# MegaShieldTrio.net
KiCad netlist of a schematic drawn in EAGLE
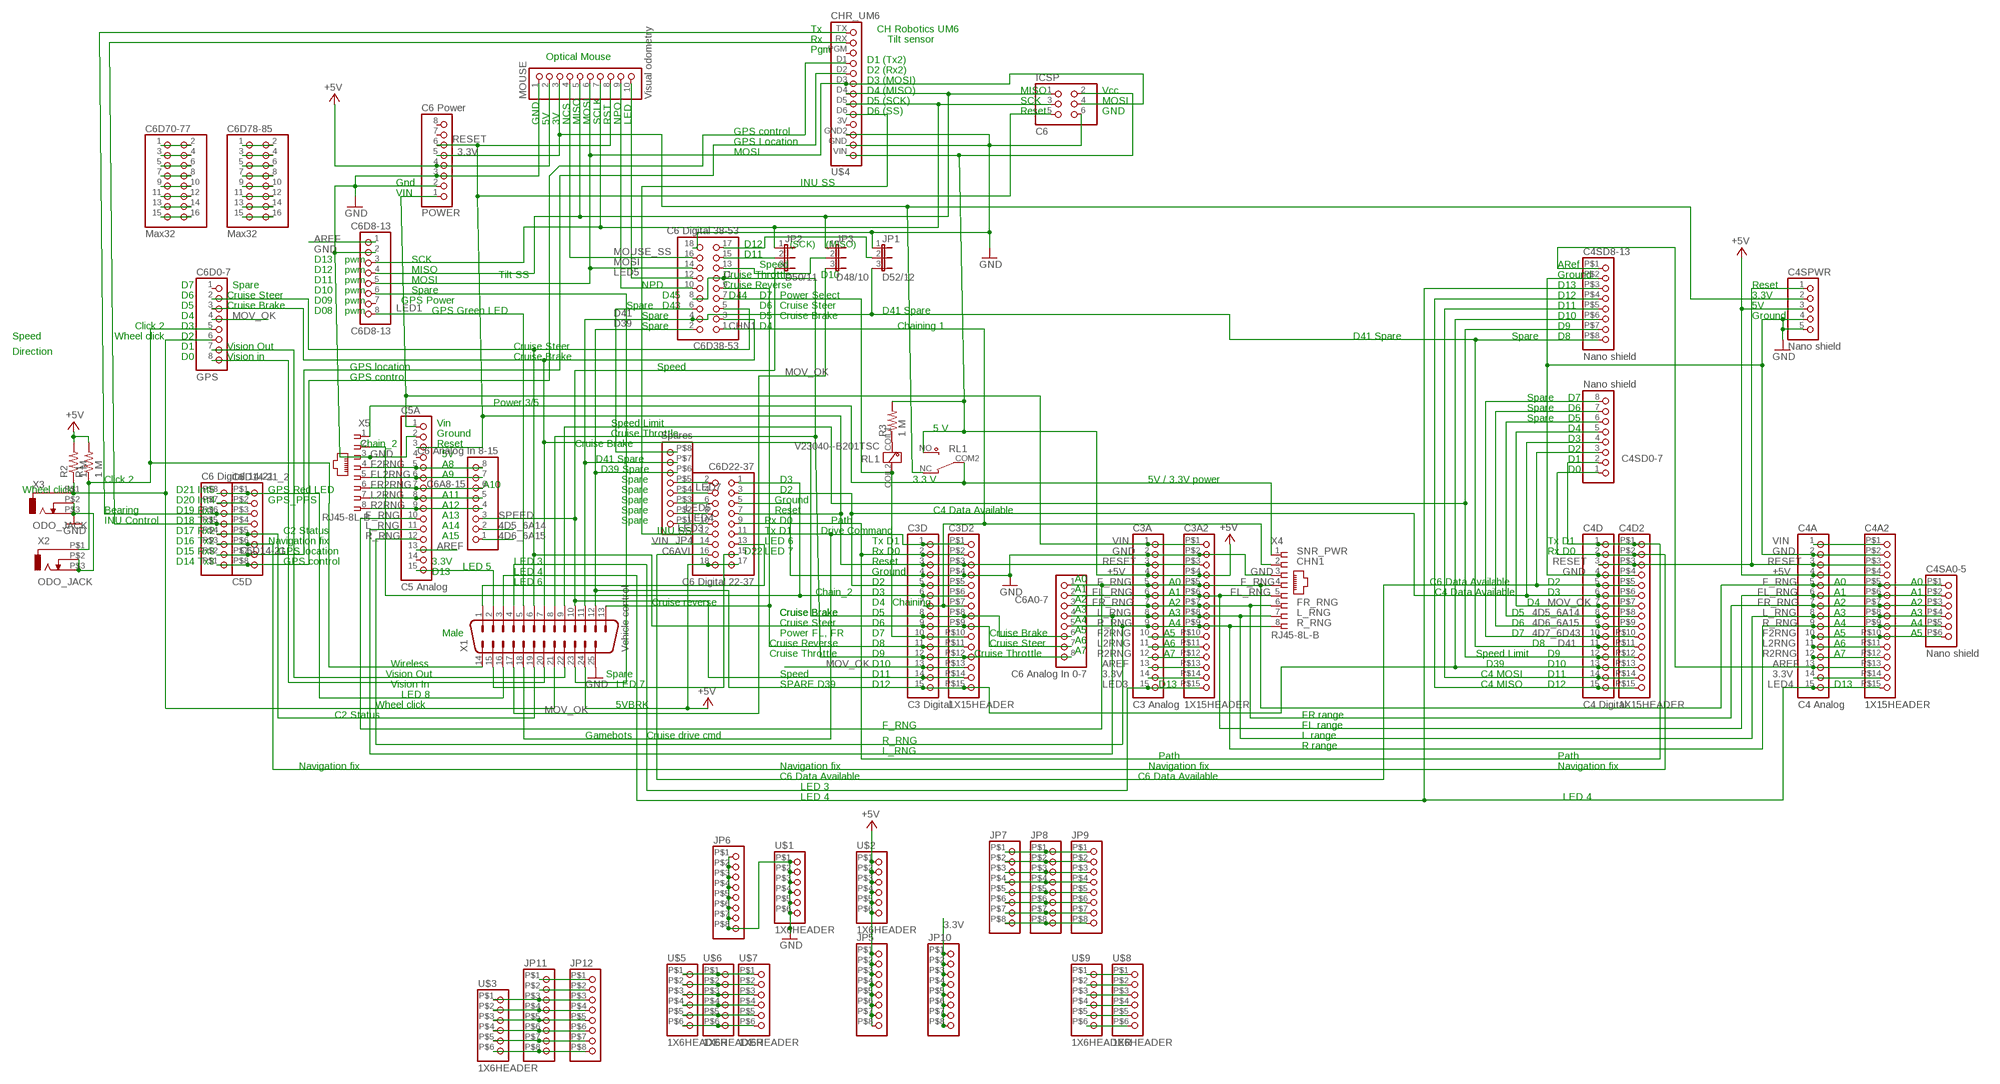
[diagram p0: schematic, sheet 1]

(export (version "E")
  (design (tool "Eeschema 10.0.6"))
  (components
    (comp (ref "C3A")
      (value "C3 Analog")
      (footprint "eagle-import:1X15")
      (libsource (lib "eagle-import") (part "PINHD-1X15"))
    )
    (comp (ref "C3A2")
      (value "1X15HEADER")
      (footprint "eagle-import:1X15HEADER")
      (libsource (lib "eagle-import") (part "1X15HEADER"))
    )
    (comp (ref "C3D")
      (value "C3 Digital")
      (footprint "eagle-import:1X15")
      (libsource (lib "eagle-import") (part "PINHD-1X15"))
    )
    (comp (ref "C3D2")
      (value "1X15HEADER")
      (footprint "eagle-import:1X15HEADER")
      (libsource (lib "eagle-import") (part "1X15HEADER"))
    )
    (comp (ref "C4A")
      (value "C4 Analog")
      (footprint "eagle-import:1X15")
      (libsource (lib "eagle-import") (part "PINHD-1X15"))
    )
    (comp (ref "C4A2")
      (value "1X15HEADER")
      (footprint "eagle-import:1X15HEADER")
      (libsource (lib "eagle-import") (part "1X15HEADER"))
    )
    (comp (ref "C4D")
      (value "C4 Digital")
      (footprint "eagle-import:1X15")
      (libsource (lib "eagle-import") (part "PINHD-1X15"))
    )
    (comp (ref "C4D2")
      (value "1X15HEADER")
      (footprint "eagle-import:1X15HEADER")
      (libsource (lib "eagle-import") (part "1X15HEADER"))
    )
    (comp (ref "C4SA0-5")
      (value "Nano shield")
      (footprint "eagle-import:1X6HEADER")
      (libsource (lib "eagle-import") (part "1X6HEADER"))
    )
    (comp (ref "C4SD0-7")
      (value "Nano shield")
      (footprint "eagle-import:1X08")
      (libsource (lib "eagle-import") (part "pinhead_PINHD-1X8"))
    )
    (comp (ref "C4SD8-13")
      (value "Nano shield")
      (footprint "eagle-import:1X8HEADER")
      (libsource (lib "eagle-import") (part "PINHD-1X8SMALL8"))
    )
    (comp (ref "C4SPWR")
      (value "Nano shield")
      (footprint "eagle-import:1X05")
      (libsource (lib "eagle-import") (part "PINHD-1X5"))
    )
    (comp (ref "C5A")
      (value "C5 Analog")
      (footprint "eagle-import:1X15")
      (libsource (lib "eagle-import") (part "PINHD-1X15"))
    )
    (comp (ref "C6A0-7")
      (value "C6 Analog In 0-7")
      (footprint "eagle-import:1X08")
      (libsource (lib "eagle-import") (part "pinhead_PINHD-1X8"))
    )
    (comp (ref "C6A8-15")
      (value "C6 Analog In 8-15")
      (footprint "eagle-import:1X08")
      (libsource (lib "eagle-import") (part "pinhead_PINHD-1X8"))
    )
    (comp (ref "C6D0-7")
      (value "GPS")
      (footprint "eagle-import:1X08")
      (libsource (lib "eagle-import") (part "pinhead_PINHD-1X8"))
    )
    (comp (ref "C6D8-13")
      (value "C6D8-13")
      (footprint "eagle-import:1X08")
      (libsource (lib "eagle-import") (part "pinhead_PINHD-1X8"))
    )
    (comp (ref "C6D14-21")
      (value "C6 Digital 14-21")
      (footprint "eagle-import:1X8HEADER")
      (libsource (lib "eagle-import") (part "PINHD-1X8SMALL8"))
    )
    (comp (ref "C6D14-21_2")
      (value "C5D")
      (footprint "eagle-import:1X8HEADER")
      (libsource (lib "eagle-import") (part "PINHD-1X8SMALL8"))
    )
    (comp (ref "C6D22-37")
      (value "C6 Digital 22-37")
      (footprint "eagle-import:2X09")
      (libsource (lib "eagle-import") (part "PINHD-2X9"))
    )
    (comp (ref "C6D38-53")
      (value "C6 Digital 38-53")
      (footprint "eagle-import:2X09")
      (libsource (lib "eagle-import") (part "PINHD-2X9"))
    )
    (comp (ref "C6D70-77")
      (value "Max32")
      (footprint "eagle-import:2X08")
      (libsource (lib "eagle-import") (part "PINHD-2X8"))
    )
    (comp (ref "C6D78-85")
      (value "Max32")
      (footprint "eagle-import:2X08")
      (libsource (lib "eagle-import") (part "PINHD-2X8"))
    )
    (comp (ref "ICSP")
      (value "C6")
      (footprint "eagle-import:2X03")
      (libsource (lib "eagle-import") (part "PINHD-2X3"))
    )
    (comp (ref "JP1")
      (value "D52/12")
      (footprint "eagle-import:JP2")
      (libsource (lib "eagle-import") (part "JP2E"))
    )
    (comp (ref "JP2")
      (value "D50/11")
      (footprint "eagle-import:JP2")
      (libsource (lib "eagle-import") (part "JP2E"))
    )
    (comp (ref "JP3")
      (value "D48/10")
      (footprint "eagle-import:JP2")
      (libsource (lib "eagle-import") (part "JP2E"))
    )
    (comp (ref "JP4")
      (value "Spares")
      (footprint "eagle-import:1X8HEADER")
      (libsource (lib "eagle-import") (part "PINHD-1X8SMALL8"))
    )
    (comp (ref "JP5")
      (value "PINHD-1X8SMALL8")
      (footprint "eagle-import:1X8HEADER")
      (libsource (lib "eagle-import") (part "PINHD-1X8SMALL8"))
    )
    (comp (ref "JP6")
      (value "PINHD-1X8SMALL8")
      (footprint "eagle-import:1X8HEADER")
      (libsource (lib "eagle-import") (part "PINHD-1X8SMALL8"))
    )
    (comp (ref "JP7")
      (value "PINHD-1X8SMALL8")
      (footprint "eagle-import:1X8HEADER")
      (libsource (lib "eagle-import") (part "PINHD-1X8SMALL8"))
    )
    (comp (ref "JP8")
      (value "PINHD-1X8SMALL8")
      (footprint "eagle-import:1X8HEADER")
      (libsource (lib "eagle-import") (part "PINHD-1X8SMALL8"))
    )
    (comp (ref "JP9")
      (value "PINHD-1X8SMALL8")
      (footprint "eagle-import:1X8HEADER")
      (libsource (lib "eagle-import") (part "PINHD-1X8SMALL8"))
    )
    (comp (ref "JP10")
      (value "PINHD-1X8SMALL8")
      (footprint "eagle-import:1X8HEADER")
      (libsource (lib "eagle-import") (part "PINHD-1X8SMALL8"))
    )
    (comp (ref "JP11")
      (value "PINHD-1X8SMALL8")
      (footprint "eagle-import:1X8HEADER")
      (libsource (lib "eagle-import") (part "PINHD-1X8SMALL8"))
    )
    (comp (ref "JP12")
      (value "PINHD-1X8SMALL8")
      (footprint "eagle-import:1X8HEADER")
      (libsource (lib "eagle-import") (part "PINHD-1X8SMALL8"))
    )
    (comp (ref "MOUSE")
      (value "Visual odometry")
      (footprint "eagle-import:1X10")
      (libsource (lib "eagle-import") (part "PINHD-1X10"))
    )
    (comp (ref "POWER")
      (value "C6 Power")
      (footprint "eagle-import:1X08")
      (libsource (lib "eagle-import") (part "pinhead_PINHD-1X8"))
    )
    (comp (ref "R1")
      (value "1 M")
      (footprint "eagle-import:0207_10")
      (libsource (lib "eagle-import") (part "R-US_0207/10"))
    )
    (comp (ref "R2")
      (value "1 M")
      (footprint "eagle-import:0207_10")
      (libsource (lib "eagle-import") (part "R-US_0207/10"))
    )
    (comp (ref "R3")
      (value "1 M")
      (footprint "eagle-import:0207_10")
      (libsource (lib "eagle-import") (part "R-US_0207/10"))
    )
    (comp (ref "RL1")
      (value "V23040--B201TSC")
      (footprint "eagle-import:TSC-112L3H")
      (libsource (lib "eagle-import") (part "V23040--B201TSC"))
    )
    (comp (ref "U$1")
      (value "1X6HEADER")
      (footprint "eagle-import:1X6HEADER")
      (libsource (lib "eagle-import") (part "1X6HEADER"))
    )
    (comp (ref "U$2")
      (value "1X6HEADER")
      (footprint "eagle-import:1X6HEADER")
      (libsource (lib "eagle-import") (part "1X6HEADER"))
    )
    (comp (ref "U$3")
      (value "1X6HEADER")
      (footprint "eagle-import:1X6HEADER")
      (libsource (lib "eagle-import") (part "1X6HEADER"))
    )
    (comp (ref "U$4")
      (value "CHR_UM6")
      (footprint "eagle-import:CHR_UM6")
      (libsource (lib "eagle-import") (part "CHR_UM6"))
    )
    (comp (ref "U$5")
      (value "1X6HEADER")
      (footprint "eagle-import:1X6HEADER")
      (libsource (lib "eagle-import") (part "1X6HEADER"))
    )
    (comp (ref "U$6")
      (value "1X6HEADER")
      (footprint "eagle-import:1X6HEADER")
      (libsource (lib "eagle-import") (part "1X6HEADER"))
    )
    (comp (ref "U$7")
      (value "1X6HEADER")
      (footprint "eagle-import:1X6HEADER")
      (libsource (lib "eagle-import") (part "1X6HEADER"))
    )
    (comp (ref "U$8")
      (value "1X6HEADER")
      (footprint "eagle-import:1X6HEADER")
      (libsource (lib "eagle-import") (part "1X6HEADER"))
    )
    (comp (ref "U$9")
      (value "1X6HEADER")
      (footprint "eagle-import:1X6HEADER")
      (libsource (lib "eagle-import") (part "1X6HEADER"))
    )
    (comp (ref "X1")
      (value "Vehicle control")
      (footprint "eagle-import:M25H")
      (libsource (lib "eagle-import") (part "M25H"))
    )
    (comp (ref "X2")
      (value "ODO_JACK")
      (footprint "eagle-import:ODO_JACK")
      (libsource (lib "eagle-import") (part "ODO_JACK"))
    )
    (comp (ref "X3")
      (value "ODO_JACK")
      (footprint "eagle-import:ODO_JACK")
      (libsource (lib "eagle-import") (part "ODO_JACK"))
    )
    (comp (ref "X4")
      (value "RJ45-8L-B")
      (footprint "eagle-import:RJ45-NO-SHIELD")
      (fields (field (name "MF") "TYCO ELECTRONICS"))
      (libsource (lib "eagle-import") (part "RJ45-8L-B"))
    )
    (comp (ref "X5")
      (value "RJ45-8L-B")
      (footprint "eagle-import:RJ45-NO-SHIELD")
      (fields (field (name "MF") "TYCO ELECTRONICS"))
      (libsource (lib "eagle-import") (part "RJ45-8L-B"))
    )
  )
  (nets
    (net (code "1") (name "+5V") (class "Default")
      (node (ref "C3A") (pin "4") (pinfunction "4_4") (pintype "passive"))
      (node (ref "C3A2") (pin "P$4") (pinfunction "4_P$4") (pintype "passive"))
      (node (ref "C4A") (pin "4") (pinfunction "4_4") (pintype "passive"))
      (node (ref "C4A2") (pin "P$4") (pinfunction "4_P$4") (pintype "passive"))
      (node (ref "C4SPWR") (pin "3") (pinfunction "3_3") (pintype "passive"))
      (node (ref "C6D22-37") (pin "17") (pinfunction "17_17") (pintype "passive"))
      (node (ref "C6D22-37") (pin "18") (pinfunction "18_18") (pintype "passive"))
      (node (ref "ICSP") (pin "2") (pinfunction "2_2") (pintype "passive"))
      (node (ref "JP5") (pin "P$1") (pinfunction "1_P$1") (pintype "passive"))
      (node (ref "JP5") (pin "P$2") (pinfunction "2_P$2") (pintype "passive"))
      (node (ref "JP5") (pin "P$3") (pinfunction "3_P$3") (pintype "passive"))
      (node (ref "JP5") (pin "P$4") (pinfunction "4_P$4") (pintype "passive"))
      (node (ref "JP5") (pin "P$5") (pinfunction "5_P$5") (pintype "passive"))
      (node (ref "JP5") (pin "P$6") (pinfunction "6_P$6") (pintype "passive"))
      (node (ref "JP5") (pin "P$7") (pinfunction "7_P$7") (pintype "passive"))
      (node (ref "JP5") (pin "P$8") (pinfunction "8_P$8") (pintype "passive"))
      (node (ref "MOUSE") (pin "2") (pinfunction "2_2") (pintype "passive"))
      (node (ref "POWER") (pin "4") (pinfunction "4_4") (pintype "passive"))
      (node (ref "R1") (pin "2") (pinfunction "2_2") (pintype "passive"))
      (node (ref "R2") (pin "2") (pinfunction "2_2") (pintype "passive"))
      (node (ref "R3") (pin "2") (pinfunction "2_2") (pintype "passive"))
      (node (ref "RL1") (pin "NO") (pinfunction "6_NO") (pintype "passive"))
      (node (ref "U$2") (pin "P$1") (pinfunction "1_P$1") (pintype "passive"))
      (node (ref "U$2") (pin "P$2") (pinfunction "2_P$2") (pintype "passive"))
      (node (ref "U$2") (pin "P$3") (pinfunction "3_P$3") (pintype "passive"))
      (node (ref "U$2") (pin "P$4") (pinfunction "4_P$4") (pintype "passive"))
      (node (ref "U$2") (pin "P$5") (pinfunction "5_P$5") (pintype "passive"))
      (node (ref "U$2") (pin "P$6") (pinfunction "6_P$6") (pintype "passive"))
      (node (ref "U$4") (pin "VIN") (pinfunction "1_VIN") (pintype "passive"))
      (node (ref "X1") (pin "24") (pinfunction "24_24") (pintype "passive"))
    )
    (net (code "2") (name "/3.3V") (class "Default")
      (node (ref "C3A") (pin "14") (pinfunction "14_14") (pintype "passive"))
      (node (ref "C3A2") (pin "P$14") (pinfunction "14_P$14") (pintype "passive"))
      (node (ref "C4A") (pin "14") (pinfunction "14_14") (pintype "passive"))
      (node (ref "C4A2") (pin "P$14") (pinfunction "14_P$14") (pintype "passive"))
      (node (ref "C4SPWR") (pin "2") (pinfunction "2_2") (pintype "passive"))
      (node (ref "JP10") (pin "P$1") (pinfunction "1_P$1") (pintype "passive"))
      (node (ref "JP10") (pin "P$2") (pinfunction "2_P$2") (pintype "passive"))
      (node (ref "JP10") (pin "P$3") (pinfunction "3_P$3") (pintype "passive"))
      (node (ref "JP10") (pin "P$4") (pinfunction "4_P$4") (pintype "passive"))
      (node (ref "JP10") (pin "P$5") (pinfunction "5_P$5") (pintype "passive"))
      (node (ref "JP10") (pin "P$6") (pinfunction "6_P$6") (pintype "passive"))
      (node (ref "JP10") (pin "P$7") (pinfunction "7_P$7") (pintype "passive"))
      (node (ref "JP10") (pin "P$8") (pinfunction "8_P$8") (pintype "passive"))
      (node (ref "MOUSE") (pin "3") (pinfunction "3_3") (pintype "passive"))
      (node (ref "POWER") (pin "5") (pinfunction "5_5") (pintype "passive"))
      (node (ref "RL1") (pin "NC") (pinfunction "4_NC") (pintype "passive"))
    )
    (net (code "3") (name "/4D5_6A14") (class "Default")
      (node (ref "C4D") (pin "8") (pinfunction "8_8") (pintype "passive"))
      (node (ref "C4D2") (pin "P$8") (pinfunction "8_P$8") (pintype "passive"))
      (node (ref "C4SD0-7") (pin "6") (pinfunction "6_6") (pintype "passive"))
      (node (ref "C6A8-15") (pin "2") (pinfunction "2_2") (pintype "passive"))
    )
    (net (code "4") (name "/4D6_6A15") (class "Default")
      (node (ref "C4D") (pin "9") (pinfunction "9_9") (pintype "passive"))
      (node (ref "C4D2") (pin "P$9") (pinfunction "9_P$9") (pintype "passive"))
      (node (ref "C4SD0-7") (pin "7") (pinfunction "7_7") (pintype "passive"))
      (node (ref "C6A8-15") (pin "1") (pinfunction "1_1") (pintype "passive"))
    )
    (net (code "5") (name "/4D7_6D43") (class "Default")
      (node (ref "C4D") (pin "10") (pinfunction "10_10") (pintype "passive"))
      (node (ref "C4D2") (pin "P$10") (pinfunction "10_P$10") (pintype "passive"))
      (node (ref "C4SD0-7") (pin "8") (pinfunction "8_8") (pintype "passive"))
    )
    (net (code "6") (name "/AREF") (class "Default")
      (node (ref "C3A") (pin "13") (pinfunction "13_13") (pintype "passive"))
      (node (ref "C3A2") (pin "P$13") (pinfunction "13_P$13") (pintype "passive"))
      (node (ref "C4A") (pin "13") (pinfunction "13_13") (pintype "passive"))
      (node (ref "C4A2") (pin "P$13") (pinfunction "13_P$13") (pintype "passive"))
      (node (ref "C4SD8-13") (pin "P$1") (pinfunction "1_P$1") (pintype "passive"))
      (node (ref "C5A") (pin "13") (pinfunction "13_13") (pintype "passive"))
      (node (ref "C6D8-13") (pin "1") (pinfunction "1_1") (pintype "passive"))
    )
    (net (code "7") (name "/C6AVL") (class "Default")
      (node (ref "C4D") (pin "5") (pinfunction "5_5") (pintype "passive"))
      (node (ref "C4D2") (pin "P$5") (pinfunction "5_P$5") (pintype "passive"))
      (node (ref "C4SD0-7") (pin "3") (pinfunction "3_3") (pintype "passive"))
      (node (ref "C6D22-37") (pin "16") (pinfunction "16_16") (pintype "passive"))
    )
    (net (code "8") (name "/CHN1") (class "Default")
      (node (ref "C3D") (pin "7") (pinfunction "7_7") (pintype "passive"))
      (node (ref "C3D2") (pin "P$7") (pinfunction "7_P$7") (pintype "passive"))
      (node (ref "C6D38-53") (pin "1") (pinfunction "1_1") (pintype "passive"))
      (node (ref "X4") (pin "2") (pinfunction "2_2") (pintype "passive"))
    )
    (net (code "9") (name "/D39") (class "Default")
      (node (ref "C3D") (pin "15") (pinfunction "15_15") (pintype "passive"))
      (node (ref "C3D2") (pin "P$15") (pinfunction "15_P$15") (pintype "passive"))
      (node (ref "C4D") (pin "13") (pinfunction "13_13") (pintype "passive"))
      (node (ref "C4D2") (pin "P$13") (pinfunction "13_P$13") (pintype "passive"))
      (node (ref "C4SD8-13") (pin "P$6") (pinfunction "6_P$6") (pintype "passive"))
      (node (ref "C6D38-53") (pin "2") (pinfunction "2_2") (pintype "passive"))
      (node (ref "JP4") (pin "P$6") (pinfunction "6_P$6") (pintype "passive"))
      (node (ref "X1") (pin "12") (pinfunction "12_12") (pintype "passive"))
    )
    (net (code "10") (name "/D41") (class "Default")
      (node (ref "C4D") (pin "11") (pinfunction "11_11") (pintype "passive"))
      (node (ref "C4D2") (pin "P$11") (pinfunction "11_P$11") (pintype "passive"))
      (node (ref "C4SD8-13") (pin "P$8") (pinfunction "8_P$8") (pintype "passive"))
      (node (ref "C6D38-53") (pin "4") (pinfunction "4_4") (pintype "passive"))
      (node (ref "JP1") (pin "3") (pinfunction "3_3") (pintype "passive"))
      (node (ref "JP4") (pin "P$7") (pinfunction "7_P$7") (pintype "passive"))
      (node (ref "X1") (pin "11") (pinfunction "11_11") (pintype "passive"))
    )
    (net (code "11") (name "/F2RNG") (class "Default")
      (node (ref "C3A") (pin "10") (pinfunction "10_10") (pintype "passive"))
      (node (ref "C3A2") (pin "P$10") (pinfunction "10_P$10") (pintype "passive"))
      (node (ref "C4A") (pin "10") (pinfunction "10_10") (pintype "passive"))
      (node (ref "C4A2") (pin "P$10") (pinfunction "10_P$10") (pintype "passive"))
      (node (ref "C4SA0-5") (pin "P$6") (pinfunction "6_P$6") (pintype "passive"))
      (node (ref "C5A") (pin "5") (pinfunction "5_5") (pintype "passive"))
      (node (ref "C6A8-15") (pin "8") (pinfunction "8_8") (pintype "passive"))
      (node (ref "X5") (pin "4") (pinfunction "4_4") (pintype "passive"))
    )
    (net (code "12") (name "/FL2RNG") (class "Default")
      (node (ref "C5A") (pin "6") (pinfunction "6_6") (pintype "passive"))
      (node (ref "C6A8-15") (pin "7") (pinfunction "7_7") (pintype "passive"))
      (node (ref "X5") (pin "5") (pinfunction "5_5") (pintype "passive"))
    )
    (net (code "13") (name "/FL_RNG") (class "Default")
      (node (ref "C3A") (pin "6") (pinfunction "6_6") (pintype "passive"))
      (node (ref "C3A2") (pin "P$6") (pinfunction "6_P$6") (pintype "passive"))
      (node (ref "C4A") (pin "6") (pinfunction "6_6") (pintype "passive"))
      (node (ref "C4A2") (pin "P$6") (pinfunction "6_P$6") (pintype "passive"))
      (node (ref "C4SA0-5") (pin "P$2") (pinfunction "2_P$2") (pintype "passive"))
      (node (ref "C6A0-7") (pin "2") (pinfunction "2_2") (pintype "passive"))
      (node (ref "X4") (pin "5") (pinfunction "5_5") (pintype "passive"))
    )
    (net (code "14") (name "/FR2RNG") (class "Default")
      (node (ref "C5A") (pin "7") (pinfunction "7_7") (pintype "passive"))
      (node (ref "C6A8-15") (pin "6") (pinfunction "6_6") (pintype "passive"))
      (node (ref "X5") (pin "6") (pinfunction "6_6") (pintype "passive"))
    )
    (net (code "15") (name "/FR_RNG") (class "Default")
      (node (ref "C3A") (pin "7") (pinfunction "7_7") (pintype "passive"))
      (node (ref "C3A2") (pin "P$7") (pinfunction "7_P$7") (pintype "passive"))
      (node (ref "C4A") (pin "7") (pinfunction "7_7") (pintype "passive"))
      (node (ref "C4A2") (pin "P$7") (pinfunction "7_P$7") (pintype "passive"))
      (node (ref "C4SA0-5") (pin "P$3") (pinfunction "3_P$3") (pintype "passive"))
      (node (ref "C6A0-7") (pin "3") (pinfunction "3_3") (pintype "passive"))
      (node (ref "X4") (pin "6") (pinfunction "6_6") (pintype "passive"))
    )
    (net (code "16") (name "/F_RNG") (class "Default")
      (node (ref "C3A") (pin "5") (pinfunction "5_5") (pintype "passive"))
      (node (ref "C3A2") (pin "P$5") (pinfunction "5_P$5") (pintype "passive"))
      (node (ref "C4A") (pin "5") (pinfunction "5_5") (pintype "passive"))
      (node (ref "C4A2") (pin "P$5") (pinfunction "5_P$5") (pintype "passive"))
      (node (ref "C4SA0-5") (pin "P$1") (pinfunction "1_P$1") (pintype "passive"))
      (node (ref "C5A") (pin "10") (pinfunction "10_10") (pintype "passive"))
      (node (ref "C6A0-7") (pin "1") (pinfunction "1_1") (pintype "passive"))
      (node (ref "X4") (pin "4") (pinfunction "4_4") (pintype "passive"))
    )
    (net (code "17") (name "/L2RNG") (class "Default")
      (node (ref "C3A") (pin "11") (pinfunction "11_11") (pintype "passive"))
      (node (ref "C3A2") (pin "P$11") (pinfunction "11_P$11") (pintype "passive"))
      (node (ref "C4A") (pin "11") (pinfunction "11_11") (pintype "passive"))
      (node (ref "C4A2") (pin "P$11") (pinfunction "11_P$11") (pintype "passive"))
      (node (ref "C5A") (pin "8") (pinfunction "8_8") (pintype "passive"))
      (node (ref "C6A8-15") (pin "5") (pinfunction "5_5") (pintype "passive"))
      (node (ref "X5") (pin "7") (pinfunction "7_7") (pintype "passive"))
    )
    (net (code "18") (name "/LED1") (class "Default")
      (node (ref "C6D8-13") (pin "8") (pinfunction "8_8") (pintype "passive"))
      (node (ref "X1") (pin "5") (pinfunction "5_5") (pintype "passive"))
    )
    (net (code "19") (name "/LED3") (class "Default")
      (node (ref "C3A") (pin "15") (pinfunction "15_15") (pintype "passive"))
      (node (ref "C3A2") (pin "P$15") (pinfunction "15_P$15") (pintype "passive"))
      (node (ref "X1") (pin "4") (pinfunction "4_4") (pintype "passive"))
    )
    (net (code "20") (name "/LED4") (class "Default")
      (node (ref "C4A") (pin "15") (pinfunction "15_15") (pintype "passive"))
      (node (ref "C4A2") (pin "P$15") (pinfunction "15_P$15") (pintype "passive"))
      (node (ref "C4SD8-13") (pin "P$3") (pinfunction "3_P$3") (pintype "passive"))
      (node (ref "X1") (pin "3") (pinfunction "3_3") (pintype "passive"))
    )
    (net (code "21") (name "/LED5") (class "Default")
      (node (ref "C5A") (pin "15") (pinfunction "15_15") (pintype "passive"))
      (node (ref "C6D38-53") (pin "12") (pinfunction "12_12") (pintype "passive"))
      (node (ref "MOUSE") (pin "10") (pinfunction "10_10") (pintype "passive"))
      (node (ref "X1") (pin "2") (pinfunction "2_2") (pintype "passive"))
    )
    (net (code "22") (name "/LED7") (class "Default")
      (node (ref "C6D22-37") (pin "15") (pinfunction "15_15") (pintype "passive"))
      (node (ref "X1") (pin "15") (pinfunction "15_15") (pintype "passive"))
    )
    (net (code "23") (name "/L_RNG") (class "Default")
      (node (ref "C3A") (pin "8") (pinfunction "8_8") (pintype "passive"))
      (node (ref "C3A2") (pin "P$8") (pinfunction "8_P$8") (pintype "passive"))
      (node (ref "C4A") (pin "8") (pinfunction "8_8") (pintype "passive"))
      (node (ref "C4A2") (pin "P$8") (pinfunction "8_P$8") (pintype "passive"))
      (node (ref "C4SA0-5") (pin "P$4") (pinfunction "4_P$4") (pintype "passive"))
      (node (ref "C5A") (pin "11") (pinfunction "11_11") (pintype "passive"))
      (node (ref "C6A0-7") (pin "4") (pinfunction "4_4") (pintype "passive"))
      (node (ref "X4") (pin "7") (pinfunction "7_7") (pintype "passive"))
    )
    (net (code "24") (name "/MOSI") (class "Default")
      (node (ref "C6D38-53") (pin "14") (pinfunction "14_14") (pintype "passive"))
      (node (ref "C6D8-13") (pin "5") (pinfunction "5_5") (pintype "passive"))
      (node (ref "ICSP") (pin "4") (pinfunction "4_4") (pintype "passive"))
      (node (ref "MOUSE") (pin "6") (pinfunction "6_6") (pintype "passive"))
      (node (ref "U$4") (pin "D3") (pinfunction "8_D3") (pintype "passive"))
    )
    (net (code "25") (name "/MOUSE_SS") (class "Default")
      (node (ref "C6D38-53") (pin "16") (pinfunction "16_16") (pintype "passive"))
      (node (ref "MOUSE") (pin "4") (pinfunction "4_4") (pintype "passive"))
    )
    (net (code "26") (name "/MOV_OK") (class "Default")
      (node (ref "C3D") (pin "13") (pinfunction "13_13") (pintype "passive"))
      (node (ref "C3D2") (pin "P$13") (pinfunction "13_P$13") (pintype "passive"))
      (node (ref "C4D") (pin "7") (pinfunction "7_7") (pintype "passive"))
      (node (ref "C4D2") (pin "P$7") (pinfunction "7_P$7") (pintype "passive"))
      (node (ref "C4SD0-7") (pin "5") (pinfunction "5_5") (pintype "passive"))
      (node (ref "C6D0-7") (pin "4") (pinfunction "4_4") (pintype "passive"))
      (node (ref "JP3") (pin "3") (pinfunction "3_3") (pintype "passive"))
      (node (ref "X1") (pin "17") (pinfunction "17_17") (pintype "passive"))
    )
    (net (code "27") (name "/R2RNG") (class "Default")
      (node (ref "C3A") (pin "12") (pinfunction "12_12") (pintype "passive"))
      (node (ref "C3A2") (pin "P$12") (pinfunction "12_P$12") (pintype "passive"))
      (node (ref "C4A") (pin "12") (pinfunction "12_12") (pintype "passive"))
      (node (ref "C4A2") (pin "P$12") (pinfunction "12_P$12") (pintype "passive"))
      (node (ref "C5A") (pin "9") (pinfunction "9_9") (pintype "passive"))
      (node (ref "C6A8-15") (pin "4") (pinfunction "4_4") (pintype "passive"))
      (node (ref "X5") (pin "8") (pinfunction "8_8") (pintype "passive"))
    )
    (net (code "28") (name "/RESET") (class "Default")
      (node (ref "C3A") (pin "3") (pinfunction "3_3") (pintype "passive"))
      (node (ref "C3A2") (pin "P$3") (pinfunction "3_P$3") (pintype "passive"))
      (node (ref "C3D") (pin "3") (pinfunction "3_3") (pintype "passive"))
      (node (ref "C3D2") (pin "P$3") (pinfunction "3_P$3") (pintype "passive"))
      (node (ref "C4A") (pin "3") (pinfunction "3_3") (pintype "passive"))
      (node (ref "C4A2") (pin "P$3") (pinfunction "3_P$3") (pintype "passive"))
      (node (ref "C4D") (pin "3") (pinfunction "3_3") (pintype "passive"))
      (node (ref "C4D2") (pin "P$3") (pinfunction "3_P$3") (pintype "passive"))
      (node (ref "C4SPWR") (pin "1") (pinfunction "1_1") (pintype "passive"))
      (node (ref "C5A") (pin "3") (pinfunction "3_3") (pintype "passive"))
      (node (ref "C6D22-37") (pin "7") (pinfunction "7_7") (pintype "passive"))
      (node (ref "ICSP") (pin "5") (pinfunction "5_5") (pintype "passive"))
      (node (ref "MOUSE") (pin "8") (pinfunction "8_8") (pintype "passive"))
      (node (ref "POWER") (pin "6") (pinfunction "6_6") (pintype "passive"))
    )
    (net (code "29") (name "/R_RNG") (class "Default")
      (node (ref "C3A") (pin "9") (pinfunction "9_9") (pintype "passive"))
      (node (ref "C3A2") (pin "P$9") (pinfunction "9_P$9") (pintype "passive"))
      (node (ref "C4A") (pin "9") (pinfunction "9_9") (pintype "passive"))
      (node (ref "C4A2") (pin "P$9") (pinfunction "9_P$9") (pintype "passive"))
      (node (ref "C4SA0-5") (pin "P$5") (pinfunction "5_P$5") (pintype "passive"))
      (node (ref "C5A") (pin "12") (pinfunction "12_12") (pintype "passive"))
      (node (ref "C6A0-7") (pin "5") (pinfunction "5_5") (pintype "passive"))
      (node (ref "X4") (pin "8") (pinfunction "8_8") (pintype "passive"))
    )
    (net (code "30") (name "/SNR_PWR") (class "Default")
      (node (ref "RL1") (pin "COM2") (pinfunction "5_COM2") (pintype "passive"))
      (node (ref "X4") (pin "1") (pinfunction "1_1") (pintype "passive"))
      (node (ref "X5") (pin "1") (pinfunction "1_1") (pintype "passive"))
    )
    (net (code "31") (name "/SPEED") (class "Default")
      (node (ref "C3D") (pin "14") (pinfunction "14_14") (pintype "passive"))
      (node (ref "C3D2") (pin "P$14") (pinfunction "14_P$14") (pintype "passive"))
      (node (ref "C6A8-15") (pin "3") (pinfunction "3_3") (pintype "passive"))
      (node (ref "JP2") (pin "3") (pinfunction "3_3") (pintype "passive"))
      (node (ref "X1") (pin "10") (pinfunction "10_10") (pintype "passive"))
    )
    (net (code "32") (name "/VIN") (class "Default")
      (node (ref "C3A") (pin "1") (pinfunction "1_1") (pintype "passive"))
      (node (ref "C3A2") (pin "P$1") (pinfunction "1_P$1") (pintype "passive"))
      (node (ref "C4A") (pin "1") (pinfunction "1_1") (pintype "passive"))
      (node (ref "C4A2") (pin "P$1") (pinfunction "1_P$1") (pintype "passive"))
      (node (ref "C5A") (pin "1") (pinfunction "1_1") (pintype "passive"))
      (node (ref "C6D22-37") (pin "14") (pinfunction "14_14") (pintype "passive"))
      (node (ref "POWER") (pin "1") (pinfunction "1_1") (pintype "passive"))
    )
    (net (code "33") (name "GND") (class "Default")
      (node (ref "C3A") (pin "2") (pinfunction "2_2") (pintype "passive"))
      (node (ref "C3A2") (pin "P$2") (pinfunction "2_P$2") (pintype "passive"))
      (node (ref "C3D") (pin "4") (pinfunction "4_4") (pintype "passive"))
      (node (ref "C3D2") (pin "P$4") (pinfunction "4_P$4") (pintype "passive"))
      (node (ref "C4A") (pin "2") (pinfunction "2_2") (pintype "passive"))
      (node (ref "C4A2") (pin "P$2") (pinfunction "2_P$2") (pintype "passive"))
      (node (ref "C4D") (pin "4") (pinfunction "4_4") (pintype "passive"))
      (node (ref "C4D2") (pin "P$4") (pinfunction "4_P$4") (pintype "passive"))
      (node (ref "C4SD8-13") (pin "P$2") (pinfunction "2_P$2") (pintype "passive"))
      (node (ref "C4SPWR") (pin "4") (pinfunction "4_4") (pintype "passive"))
      (node (ref "C4SPWR") (pin "5") (pinfunction "5_5") (pintype "passive"))
      (node (ref "C5A") (pin "2") (pinfunction "2_2") (pintype "passive"))
      (node (ref "C6D22-37") (pin "5") (pinfunction "5_5") (pintype "passive"))
      (node (ref "C6D38-53") (pin "18") (pinfunction "18_18") (pintype "passive"))
      (node (ref "C6D8-13") (pin "2") (pinfunction "2_2") (pintype "passive"))
      (node (ref "ICSP") (pin "6") (pinfunction "6_6") (pintype "passive"))
      (node (ref "JP1") (pin "1") (pinfunction "1_1") (pintype "passive"))
      (node (ref "JP6") (pin "P$1") (pinfunction "1_P$1") (pintype "passive"))
      (node (ref "JP6") (pin "P$2") (pinfunction "2_P$2") (pintype "passive"))
      (node (ref "JP6") (pin "P$3") (pinfunction "3_P$3") (pintype "passive"))
      (node (ref "JP6") (pin "P$4") (pinfunction "4_P$4") (pintype "passive"))
      (node (ref "JP6") (pin "P$5") (pinfunction "5_P$5") (pintype "passive"))
      (node (ref "JP6") (pin "P$6") (pinfunction "6_P$6") (pintype "passive"))
      (node (ref "JP6") (pin "P$7") (pinfunction "7_P$7") (pintype "passive"))
      (node (ref "JP6") (pin "P$8") (pinfunction "8_P$8") (pintype "passive"))
      (node (ref "MOUSE") (pin "1") (pinfunction "1_1") (pintype "passive"))
      (node (ref "POWER") (pin "2") (pinfunction "2_2") (pintype "passive"))
      (node (ref "POWER") (pin "3") (pinfunction "3_3") (pintype "passive"))
      (node (ref "U$1") (pin "P$1") (pinfunction "1_P$1") (pintype "passive"))
      (node (ref "U$1") (pin "P$2") (pinfunction "2_P$2") (pintype "passive"))
      (node (ref "U$1") (pin "P$3") (pinfunction "3_P$3") (pintype "passive"))
      (node (ref "U$1") (pin "P$4") (pinfunction "4_P$4") (pintype "passive"))
      (node (ref "U$1") (pin "P$5") (pinfunction "5_P$5") (pintype "passive"))
      (node (ref "U$1") (pin "P$6") (pinfunction "6_P$6") (pintype "passive"))
      (node (ref "U$4") (pin "GND") (pinfunction "2_GND") (pintype "passive"))
      (node (ref "U$4") (pin "GND2") (pinfunction "3_GND2") (pintype "passive"))
      (node (ref "X1") (pin "25") (pinfunction "25_25") (pintype "passive"))
      (node (ref "X2") (pin "P$2") (pinfunction "2_P$2") (pintype "passive"))
      (node (ref "X2") (pin "P$3") (pinfunction "3_P$3") (pintype "passive"))
      (node (ref "X3") (pin "P$2") (pinfunction "2_P$2") (pintype "passive"))
      (node (ref "X3") (pin "P$3") (pinfunction "3_P$3") (pintype "passive"))
      (node (ref "X4") (pin "3") (pinfunction "3_3") (pintype "passive"))
      (node (ref "X5") (pin "3") (pinfunction "3_3") (pintype "passive"))
    )
    (net (code "34") (name "Net-(C3D2-1)") (class "Default")
      (node (ref "C3D") (pin "1") (pinfunction "1_1") (pintype "passive"))
      (node (ref "C3D2") (pin "P$1") (pinfunction "1_P$1") (pintype "passive"))
      (node (ref "C6D22-37") (pin "11") (pinfunction "11_11") (pintype "passive"))
      (node (ref "X1") (pin "18") (pinfunction "18_18") (pintype "passive"))
    )
    (net (code "35") (name "Net-(C3D2-2)") (class "Default")
      (node (ref "C3D") (pin "2") (pinfunction "2_2") (pintype "passive"))
      (node (ref "C3D2") (pin "P$2") (pinfunction "2_P$2") (pintype "passive"))
      (node (ref "C4D") (pin "1") (pinfunction "1_1") (pintype "passive"))
      (node (ref "C4D2") (pin "P$1") (pinfunction "1_P$1") (pintype "passive"))
      (node (ref "C4SD0-7") (pin "2") (pinfunction "2_2") (pintype "passive"))
      (node (ref "C6D22-37") (pin "9") (pinfunction "9_9") (pintype "passive"))
    )
    (net (code "36") (name "Net-(C3D2-5)") (class "Default")
      (node (ref "C3D") (pin "5") (pinfunction "5_5") (pintype "passive"))
      (node (ref "C3D2") (pin "P$5") (pinfunction "5_P$5") (pintype "passive"))
      (node (ref "C4D") (pin "6") (pinfunction "6_6") (pintype "passive"))
      (node (ref "C4D2") (pin "P$6") (pinfunction "6_P$6") (pintype "passive"))
      (node (ref "C4SD0-7") (pin "4") (pinfunction "4_4") (pintype "passive"))
      (node (ref "C6D22-37") (pin "3") (pinfunction "3_3") (pintype "passive"))
    )
    (net (code "37") (name "Net-(C3D2-6)") (class "Default")
      (node (ref "C3D") (pin "6") (pinfunction "6_6") (pintype "passive"))
      (node (ref "C3D2") (pin "P$6") (pinfunction "6_P$6") (pintype "passive"))
      (node (ref "C6D22-37") (pin "1") (pinfunction "1_1") (pintype "passive"))
      (node (ref "X5") (pin "2") (pinfunction "2_2") (pintype "passive"))
    )
    (net (code "38") (name "Net-(C3D2-8)") (class "Default")
      (node (ref "C3D") (pin "8") (pinfunction "8_8") (pintype "passive"))
      (node (ref "C3D2") (pin "P$8") (pinfunction "8_P$8") (pintype "passive"))
      (node (ref "C6A0-7") (pin "6") (pinfunction "6_6") (pintype "passive"))
      (node (ref "C6D0-7") (pin "3") (pinfunction "3_3") (pintype "passive"))
      (node (ref "C6D38-53") (pin "3") (pinfunction "3_3") (pintype "passive"))
      (node (ref "X1") (pin "7") (pinfunction "7_7") (pintype "passive"))
    )
    (net (code "39") (name "Net-(C3D2-9)") (class "Default")
      (node (ref "C3D") (pin "9") (pinfunction "9_9") (pintype "passive"))
      (node (ref "C3D2") (pin "P$9") (pinfunction "9_P$9") (pintype "passive"))
      (node (ref "C6A0-7") (pin "7") (pinfunction "7_7") (pintype "passive"))
      (node (ref "C6D0-7") (pin "2") (pinfunction "2_2") (pintype "passive"))
      (node (ref "C6D38-53") (pin "5") (pinfunction "5_5") (pintype "passive"))
      (node (ref "X1") (pin "6") (pinfunction "6_6") (pintype "passive"))
    )
    (net (code "40") (name "Net-(C3D2-10)") (class "Default")
      (node (ref "C3D") (pin "10") (pinfunction "10_10") (pintype "passive"))
      (node (ref "C3D2") (pin "P$10") (pinfunction "10_P$10") (pintype "passive"))
      (node (ref "C6D38-53") (pin "7") (pinfunction "7_7") (pintype "passive"))
      (node (ref "RL1") (pin "COIL2") (pinfunction "2_COIL2") (pintype "passive"))
    )
    (net (code "41") (name "Net-(C3D2-11)") (class "Default")
      (node (ref "C3D") (pin "11") (pinfunction "11_11") (pintype "passive"))
      (node (ref "C3D2") (pin "P$11") (pinfunction "11_P$11") (pintype "passive"))
      (node (ref "C6D38-53") (pin "9") (pinfunction "9_9") (pintype "passive"))
      (node (ref "X1") (pin "13") (pinfunction "13_13") (pintype "passive"))
    )
    (net (code "42") (name "Net-(C3D2-12)") (class "Default")
      (node (ref "C3D") (pin "12") (pinfunction "12_12") (pintype "passive"))
      (node (ref "C3D2") (pin "P$12") (pinfunction "12_P$12") (pintype "passive"))
      (node (ref "C6A0-7") (pin "8") (pinfunction "8_8") (pintype "passive"))
      (node (ref "C6D38-53") (pin "11") (pinfunction "11_11") (pintype "passive"))
      (node (ref "C6D38-53") (pin "8") (pinfunction "8_8") (pintype "passive"))
      (node (ref "X1") (pin "8") (pinfunction "8_8") (pintype "passive"))
    )
    (net (code "43") (name "Net-(C4D2-2)") (class "Default")
      (node (ref "C4D") (pin "2") (pinfunction "2_2") (pintype "passive"))
      (node (ref "C4D2") (pin "P$2") (pinfunction "2_P$2") (pintype "passive"))
      (node (ref "C4SD0-7") (pin "1") (pinfunction "1_1") (pintype "passive"))
      (node (ref "C6D14-21") (pin "P$3") (pinfunction "3_P$3") (pintype "passive"))
      (node (ref "C6D14-21_2") (pin "P$6") (pinfunction "6_P$6") (pintype "passive"))
    )
    (net (code "44") (name "Net-(C4D2-12)") (class "Default")
      (node (ref "C4D") (pin "12") (pinfunction "12_12") (pintype "passive"))
      (node (ref "C4D2") (pin "P$12") (pinfunction "12_P$12") (pintype "passive"))
      (node (ref "C4SD8-13") (pin "P$7") (pinfunction "7_P$7") (pintype "passive"))
      (node (ref "X1") (pin "9") (pinfunction "9_9") (pintype "passive"))
    )
    (net (code "45") (name "Net-(C4D2-14)") (class "Default")
      (node (ref "C4D") (pin "14") (pinfunction "14_14") (pintype "passive"))
      (node (ref "C4D2") (pin "P$14") (pinfunction "14_P$14") (pintype "passive"))
      (node (ref "C4SD8-13") (pin "P$5") (pinfunction "5_P$5") (pintype "passive"))
    )
    (net (code "46") (name "Net-(C4D2-15)") (class "Default")
      (node (ref "C4D") (pin "15") (pinfunction "15_15") (pintype "passive"))
      (node (ref "C4D2") (pin "P$15") (pinfunction "15_P$15") (pintype "passive"))
      (node (ref "C4SD8-13") (pin "P$4") (pinfunction "4_P$4") (pintype "passive"))
    )
    (net (code "47") (name "Net-(C6D0-7-Pad7)") (class "Default")
      (node (ref "C6D0-7") (pin "7") (pinfunction "7_7") (pintype "passive"))
      (node (ref "X1") (pin "22") (pinfunction "22_22") (pintype "passive"))
    )
    (net (code "48") (name "Net-(C6D0-7-Pad8)") (class "Default")
      (node (ref "C6D0-7") (pin "8") (pinfunction "8_8") (pintype "passive"))
      (node (ref "X1") (pin "20") (pinfunction "20_20") (pintype "passive"))
    )
    (net (code "49") (name "Net-(C6D8-13-Pad6)") (class "Default")
      (node (ref "C6D8-13") (pin "6") (pinfunction "6_6") (pintype "passive"))
      (node (ref "X1") (pin "23") (pinfunction "23_23") (pintype "passive"))
    )
    (net (code "50") (name "Net-(C6D14-21-1)") (class "Default")
      (node (ref "C6D14-21") (pin "P$1") (pinfunction "1_P$1") (pintype "passive"))
      (node (ref "C6D14-21_2") (pin "P$8") (pinfunction "8_P$8") (pintype "passive"))
      (node (ref "U$4") (pin "D1") (pinfunction "10_D1") (pintype "passive"))
    )
    (net (code "51") (name "Net-(C6D14-21-2)") (class "Default")
      (node (ref "C6D14-21") (pin "P$2") (pinfunction "2_P$2") (pintype "passive"))
      (node (ref "C6D14-21_2") (pin "P$7") (pinfunction "7_P$7") (pintype "passive"))
      (node (ref "U$4") (pin "D2") (pinfunction "9_D2") (pintype "passive"))
    )
    (net (code "52") (name "Net-(C6D14-21-4)") (class "Default")
      (node (ref "C6D14-21") (pin "P$4") (pinfunction "4_P$4") (pintype "passive"))
      (node (ref "C6D14-21_2") (pin "P$5") (pinfunction "5_P$5") (pintype "passive"))
      (node (ref "X1") (pin "19") (pinfunction "19_19") (pintype "passive"))
    )
    (net (code "53") (name "Net-(C6D14-21-5)") (class "Default")
      (node (ref "C6D14-21") (pin "P$5") (pinfunction "5_P$5") (pintype "passive"))
      (node (ref "C6D14-21_2") (pin "P$4") (pinfunction "4_P$4") (pintype "passive"))
      (node (ref "U$4") (pin "RX") (pinfunction "12_RX") (pintype "passive"))
    )
    (net (code "54") (name "Net-(C6D14-21-6)") (class "Default")
      (node (ref "C6D14-21") (pin "P$6") (pinfunction "6_P$6") (pintype "passive"))
      (node (ref "C6D14-21_2") (pin "P$3") (pinfunction "3_P$3") (pintype "passive"))
      (node (ref "U$4") (pin "TX") (pinfunction "13_TX") (pintype "passive"))
    )
    (net (code "55") (name "Net-(C6D14-21-7)") (class "Default")
      (node (ref "C6D14-21") (pin "P$7") (pinfunction "7_P$7") (pintype "passive"))
      (node (ref "C6D14-21_2") (pin "P$2") (pinfunction "2_P$2") (pintype "passive"))
    )
    (net (code "56") (name "Net-(C6D14-21-8)") (class "Default")
      (node (ref "C6D14-21") (pin "P$8") (pinfunction "8_P$8") (pintype "passive"))
      (node (ref "C6D14-21_2") (pin "P$1") (pinfunction "1_P$1") (pintype "passive"))
      (node (ref "X1") (pin "16") (pinfunction "16_16") (pintype "passive"))
    )
    (net (code "57") (name "Net-(C6D22-37-Pad13)") (class "Default")
      (node (ref "C6D22-37") (pin "13") (pinfunction "13_13") (pintype "passive"))
      (node (ref "X1") (pin "1") (pinfunction "1_1") (pintype "passive"))
    )
    (net (code "58") (name "Net-(C6D38-53-Pad10)") (class "Default")
      (node (ref "C6D38-53") (pin "10") (pinfunction "10_10") (pintype "passive"))
      (node (ref "MOUSE") (pin "9") (pinfunction "9_9") (pintype "passive"))
    )
    (net (code "59") (name "Net-(C6D38-53-Pad13)") (class "Default")
      (node (ref "C6D38-53") (pin "13") (pinfunction "13_13") (pintype "passive"))
      (node (ref "JP3") (pin "2") (pinfunction "2_2") (pintype "passive"))
    )
    (net (code "60") (name "Net-(C6D38-53-Pad15)") (class "Default")
      (node (ref "C6D38-53") (pin "15") (pinfunction "15_15") (pintype "passive"))
      (node (ref "JP2") (pin "2") (pinfunction "2_2") (pintype "passive"))
    )
    (net (code "61") (name "Net-(C6D38-53-Pad17)") (class "Default")
      (node (ref "C6D38-53") (pin "17") (pinfunction "17_17") (pintype "passive"))
      (node (ref "JP1") (pin "2") (pinfunction "2_2") (pintype "passive"))
    )
    (net (code "62") (name "Net-(C6D70-77-Pad1)") (class "Default")
      (node (ref "C6D70-77") (pin "1") (pinfunction "1_1") (pintype "passive"))
      (node (ref "C6D70-77") (pin "2") (pinfunction "2_2") (pintype "passive"))
    )
    (net (code "63") (name "Net-(C6D70-77-Pad3)") (class "Default")
      (node (ref "C6D70-77") (pin "3") (pinfunction "3_3") (pintype "passive"))
      (node (ref "C6D70-77") (pin "4") (pinfunction "4_4") (pintype "passive"))
    )
    (net (code "64") (name "Net-(C6D70-77-Pad5)") (class "Default")
      (node (ref "C6D70-77") (pin "5") (pinfunction "5_5") (pintype "passive"))
      (node (ref "C6D70-77") (pin "6") (pinfunction "6_6") (pintype "passive"))
    )
    (net (code "65") (name "Net-(C6D70-77-Pad7)") (class "Default")
      (node (ref "C6D70-77") (pin "7") (pinfunction "7_7") (pintype "passive"))
      (node (ref "C6D70-77") (pin "8") (pinfunction "8_8") (pintype "passive"))
    )
    (net (code "66") (name "Net-(C6D70-77-Pad10)") (class "Default")
      (node (ref "C6D70-77") (pin "10") (pinfunction "10_10") (pintype "passive"))
      (node (ref "C6D70-77") (pin "9") (pinfunction "9_9") (pintype "passive"))
    )
    (net (code "67") (name "Net-(C6D70-77-Pad11)") (class "Default")
      (node (ref "C6D70-77") (pin "11") (pinfunction "11_11") (pintype "passive"))
      (node (ref "C6D70-77") (pin "12") (pinfunction "12_12") (pintype "passive"))
    )
    (net (code "68") (name "Net-(C6D70-77-Pad13)") (class "Default")
      (node (ref "C6D70-77") (pin "13") (pinfunction "13_13") (pintype "passive"))
      (node (ref "C6D70-77") (pin "14") (pinfunction "14_14") (pintype "passive"))
    )
    (net (code "69") (name "Net-(C6D70-77-Pad15)") (class "Default")
      (node (ref "C6D70-77") (pin "15") (pinfunction "15_15") (pintype "passive"))
      (node (ref "C6D70-77") (pin "16") (pinfunction "16_16") (pintype "passive"))
    )
    (net (code "70") (name "Net-(C6D78-85-Pad1)") (class "Default")
      (node (ref "C6D78-85") (pin "1") (pinfunction "1_1") (pintype "passive"))
      (node (ref "C6D78-85") (pin "2") (pinfunction "2_2") (pintype "passive"))
    )
    (net (code "71") (name "Net-(C6D78-85-Pad3)") (class "Default")
      (node (ref "C6D78-85") (pin "3") (pinfunction "3_3") (pintype "passive"))
      (node (ref "C6D78-85") (pin "4") (pinfunction "4_4") (pintype "passive"))
    )
    (net (code "72") (name "Net-(C6D78-85-Pad5)") (class "Default")
      (node (ref "C6D78-85") (pin "5") (pinfunction "5_5") (pintype "passive"))
      (node (ref "C6D78-85") (pin "6") (pinfunction "6_6") (pintype "passive"))
    )
    (net (code "73") (name "Net-(C6D78-85-Pad7)") (class "Default")
      (node (ref "C6D78-85") (pin "7") (pinfunction "7_7") (pintype "passive"))
      (node (ref "C6D78-85") (pin "8") (pinfunction "8_8") (pintype "passive"))
    )
    (net (code "74") (name "Net-(C6D78-85-Pad10)") (class "Default")
      (node (ref "C6D78-85") (pin "10") (pinfunction "10_10") (pintype "passive"))
      (node (ref "C6D78-85") (pin "9") (pinfunction "9_9") (pintype "passive"))
    )
    (net (code "75") (name "Net-(C6D78-85-Pad11)") (class "Default")
      (node (ref "C6D78-85") (pin "11") (pinfunction "11_11") (pintype "passive"))
      (node (ref "C6D78-85") (pin "12") (pinfunction "12_12") (pintype "passive"))
    )
    (net (code "76") (name "Net-(C6D78-85-Pad13)") (class "Default")
      (node (ref "C6D78-85") (pin "13") (pinfunction "13_13") (pintype "passive"))
      (node (ref "C6D78-85") (pin "14") (pinfunction "14_14") (pintype "passive"))
    )
    (net (code "77") (name "Net-(C6D78-85-Pad15)") (class "Default")
      (node (ref "C6D78-85") (pin "15") (pinfunction "15_15") (pintype "passive"))
      (node (ref "C6D78-85") (pin "16") (pinfunction "16_16") (pintype "passive"))
    )
    (net (code "78") (name "Net-(JP4-1)") (class "Default")
      (node (ref "C6D22-37") (pin "10") (pinfunction "10_10") (pintype "passive"))
      (node (ref "JP4") (pin "P$1") (pinfunction "1_P$1") (pintype "passive"))
    )
    (net (code "79") (name "Net-(JP4-2)") (class "Default")
      (node (ref "C6D22-37") (pin "8") (pinfunction "8_8") (pintype "passive"))
      (node (ref "JP4") (pin "P$2") (pinfunction "2_P$2") (pintype "passive"))
    )
    (net (code "80") (name "Net-(JP4-3)") (class "Default")
      (node (ref "C6D22-37") (pin "6") (pinfunction "6_6") (pintype "passive"))
      (node (ref "JP4") (pin "P$3") (pinfunction "3_P$3") (pintype "passive"))
    )
    (net (code "81") (name "Net-(JP4-4)") (class "Default")
      (node (ref "C6D22-37") (pin "4") (pinfunction "4_4") (pintype "passive"))
      (node (ref "JP4") (pin "P$4") (pinfunction "4_P$4") (pintype "passive"))
    )
    (net (code "82") (name "Net-(JP4-5)") (class "Default")
      (node (ref "C6D22-37") (pin "2") (pinfunction "2_2") (pintype "passive"))
      (node (ref "JP4") (pin "P$5") (pinfunction "5_P$5") (pintype "passive"))
    )
    (net (code "83") (name "Net-(JP4-8)") (class "Default")
      (node (ref "C6D38-53") (pin "6") (pinfunction "6_6") (pintype "passive"))
      (node (ref "JP4") (pin "P$8") (pinfunction "8_P$8") (pintype "passive"))
    )
    (net (code "84") (name "Net-(JP7-1)") (class "Default")
      (node (ref "JP7") (pin "P$1") (pinfunction "1_P$1") (pintype "passive"))
      (node (ref "JP8") (pin "P$1") (pinfunction "1_P$1") (pintype "passive"))
      (node (ref "JP9") (pin "P$1") (pinfunction "1_P$1") (pintype "passive"))
    )
    (net (code "85") (name "Net-(JP7-2)") (class "Default")
      (node (ref "JP7") (pin "P$2") (pinfunction "2_P$2") (pintype "passive"))
      (node (ref "JP8") (pin "P$2") (pinfunction "2_P$2") (pintype "passive"))
      (node (ref "JP9") (pin "P$2") (pinfunction "2_P$2") (pintype "passive"))
    )
    (net (code "86") (name "Net-(JP7-3)") (class "Default")
      (node (ref "JP7") (pin "P$3") (pinfunction "3_P$3") (pintype "passive"))
      (node (ref "JP8") (pin "P$3") (pinfunction "3_P$3") (pintype "passive"))
      (node (ref "JP9") (pin "P$3") (pinfunction "3_P$3") (pintype "passive"))
    )
    (net (code "87") (name "Net-(JP7-4)") (class "Default")
      (node (ref "JP7") (pin "P$4") (pinfunction "4_P$4") (pintype "passive"))
      (node (ref "JP8") (pin "P$4") (pinfunction "4_P$4") (pintype "passive"))
      (node (ref "JP9") (pin "P$4") (pinfunction "4_P$4") (pintype "passive"))
    )
    (net (code "88") (name "Net-(JP7-5)") (class "Default")
      (node (ref "JP7") (pin "P$5") (pinfunction "5_P$5") (pintype "passive"))
      (node (ref "JP8") (pin "P$5") (pinfunction "5_P$5") (pintype "passive"))
      (node (ref "JP9") (pin "P$5") (pinfunction "5_P$5") (pintype "passive"))
    )
    (net (code "89") (name "Net-(JP7-6)") (class "Default")
      (node (ref "JP7") (pin "P$6") (pinfunction "6_P$6") (pintype "passive"))
      (node (ref "JP8") (pin "P$6") (pinfunction "6_P$6") (pintype "passive"))
      (node (ref "JP9") (pin "P$6") (pinfunction "6_P$6") (pintype "passive"))
    )
    (net (code "90") (name "Net-(JP7-7)") (class "Default")
      (node (ref "JP7") (pin "P$7") (pinfunction "7_P$7") (pintype "passive"))
      (node (ref "JP8") (pin "P$7") (pinfunction "7_P$7") (pintype "passive"))
      (node (ref "JP9") (pin "P$7") (pinfunction "7_P$7") (pintype "passive"))
    )
    (net (code "91") (name "Net-(JP7-8)") (class "Default")
      (node (ref "JP7") (pin "P$8") (pinfunction "8_P$8") (pintype "passive"))
      (node (ref "JP8") (pin "P$8") (pinfunction "8_P$8") (pintype "passive"))
      (node (ref "JP9") (pin "P$8") (pinfunction "8_P$8") (pintype "passive"))
    )
    (net (code "92") (name "Net-(JP11-1)") (class "Default")
      (node (ref "JP11") (pin "P$1") (pinfunction "1_P$1") (pintype "passive"))
      (node (ref "JP12") (pin "P$1") (pinfunction "1_P$1") (pintype "passive"))
    )
    (net (code "93") (name "Net-(JP11-2)") (class "Default")
      (node (ref "JP11") (pin "P$2") (pinfunction "2_P$2") (pintype "passive"))
      (node (ref "JP12") (pin "P$2") (pinfunction "2_P$2") (pintype "passive"))
    )
    (net (code "94") (name "Net-(JP11-3)") (class "Default")
      (node (ref "JP11") (pin "P$3") (pinfunction "3_P$3") (pintype "passive"))
      (node (ref "JP12") (pin "P$3") (pinfunction "3_P$3") (pintype "passive"))
      (node (ref "U$3") (pin "P$1") (pinfunction "1_P$1") (pintype "passive"))
    )
    (net (code "95") (name "Net-(JP11-4)") (class "Default")
      (node (ref "JP11") (pin "P$4") (pinfunction "4_P$4") (pintype "passive"))
      (node (ref "JP12") (pin "P$4") (pinfunction "4_P$4") (pintype "passive"))
      (node (ref "U$3") (pin "P$2") (pinfunction "2_P$2") (pintype "passive"))
    )
    (net (code "96") (name "Net-(JP11-5)") (class "Default")
      (node (ref "JP11") (pin "P$5") (pinfunction "5_P$5") (pintype "passive"))
      (node (ref "JP12") (pin "P$5") (pinfunction "5_P$5") (pintype "passive"))
      (node (ref "U$3") (pin "P$3") (pinfunction "3_P$3") (pintype "passive"))
    )
    (net (code "97") (name "Net-(JP11-6)") (class "Default")
      (node (ref "JP11") (pin "P$6") (pinfunction "6_P$6") (pintype "passive"))
      (node (ref "JP12") (pin "P$6") (pinfunction "6_P$6") (pintype "passive"))
      (node (ref "U$3") (pin "P$4") (pinfunction "4_P$4") (pintype "passive"))
    )
    (net (code "98") (name "Net-(JP11-7)") (class "Default")
      (node (ref "JP11") (pin "P$7") (pinfunction "7_P$7") (pintype "passive"))
      (node (ref "JP12") (pin "P$7") (pinfunction "7_P$7") (pintype "passive"))
      (node (ref "U$3") (pin "P$5") (pinfunction "5_P$5") (pintype "passive"))
    )
    (net (code "99") (name "Net-(JP11-8)") (class "Default")
      (node (ref "JP11") (pin "P$8") (pinfunction "8_P$8") (pintype "passive"))
      (node (ref "JP12") (pin "P$8") (pinfunction "8_P$8") (pintype "passive"))
      (node (ref "U$3") (pin "P$6") (pinfunction "6_P$6") (pintype "passive"))
    )
    (net (code "100") (name "Net-(RL1A-1)") (class "Default")
      (node (ref "R3") (pin "1") (pinfunction "1_1") (pintype "passive"))
      (node (ref "RL1") (pin "COIL1") (pinfunction "1_COIL1") (pintype "passive"))
    )
    (net (code "101") (name "Net-(U$4-5)") (class "Default")
      (node (ref "C6D22-37") (pin "12") (pinfunction "12_12") (pintype "passive"))
      (node (ref "U$4") (pin "D6") (pinfunction "5_D6") (pintype "passive"))
    )
    (net (code "102") (name "Net-(U$4-6)") (class "Default")
      (node (ref "C6D8-13") (pin "3") (pinfunction "3_3") (pintype "passive"))
      (node (ref "ICSP") (pin "3") (pinfunction "3_3") (pintype "passive"))
      (node (ref "JP2") (pin "1") (pinfunction "1_1") (pintype "passive"))
      (node (ref "MOUSE") (pin "7") (pinfunction "7_7") (pintype "passive"))
      (node (ref "U$4") (pin "D5") (pinfunction "6_D5") (pintype "passive"))
    )
    (net (code "103") (name "Net-(U$4-7)") (class "Default")
      (node (ref "C6D8-13") (pin "4") (pinfunction "4_4") (pintype "passive"))
      (node (ref "ICSP") (pin "1") (pinfunction "1_1") (pintype "passive"))
      (node (ref "JP3") (pin "1") (pinfunction "1_1") (pintype "passive"))
      (node (ref "MOUSE") (pin "5") (pinfunction "5_5") (pintype "passive"))
      (node (ref "U$4") (pin "D4") (pinfunction "7_D4") (pintype "passive"))
    )
    (net (code "104") (name "Net-(U$5-1)") (class "Default")
      (node (ref "U$5") (pin "P$1") (pinfunction "1_P$1") (pintype "passive"))
      (node (ref "U$6") (pin "P$1") (pinfunction "1_P$1") (pintype "passive"))
      (node (ref "U$7") (pin "P$1") (pinfunction "1_P$1") (pintype "passive"))
    )
    (net (code "105") (name "Net-(U$5-2)") (class "Default")
      (node (ref "U$5") (pin "P$2") (pinfunction "2_P$2") (pintype "passive"))
      (node (ref "U$6") (pin "P$2") (pinfunction "2_P$2") (pintype "passive"))
      (node (ref "U$7") (pin "P$2") (pinfunction "2_P$2") (pintype "passive"))
    )
    (net (code "106") (name "Net-(U$5-3)") (class "Default")
      (node (ref "U$5") (pin "P$3") (pinfunction "3_P$3") (pintype "passive"))
      (node (ref "U$6") (pin "P$3") (pinfunction "3_P$3") (pintype "passive"))
      (node (ref "U$7") (pin "P$3") (pinfunction "3_P$3") (pintype "passive"))
    )
    (net (code "107") (name "Net-(U$5-4)") (class "Default")
      (node (ref "U$5") (pin "P$4") (pinfunction "4_P$4") (pintype "passive"))
      (node (ref "U$6") (pin "P$4") (pinfunction "4_P$4") (pintype "passive"))
      (node (ref "U$7") (pin "P$4") (pinfunction "4_P$4") (pintype "passive"))
    )
    (net (code "108") (name "Net-(U$5-5)") (class "Default")
      (node (ref "U$5") (pin "P$5") (pinfunction "5_P$5") (pintype "passive"))
      (node (ref "U$6") (pin "P$5") (pinfunction "5_P$5") (pintype "passive"))
      (node (ref "U$7") (pin "P$5") (pinfunction "5_P$5") (pintype "passive"))
    )
    (net (code "109") (name "Net-(U$5-6)") (class "Default")
      (node (ref "U$5") (pin "P$6") (pinfunction "6_P$6") (pintype "passive"))
      (node (ref "U$6") (pin "P$6") (pinfunction "6_P$6") (pintype "passive"))
      (node (ref "U$7") (pin "P$6") (pinfunction "6_P$6") (pintype "passive"))
    )
    (net (code "110") (name "Net-(U$8-1)") (class "Default")
      (node (ref "U$8") (pin "P$1") (pinfunction "1_P$1") (pintype "passive"))
      (node (ref "U$9") (pin "P$1") (pinfunction "1_P$1") (pintype "passive"))
    )
    (net (code "111") (name "Net-(U$8-2)") (class "Default")
      (node (ref "U$8") (pin "P$2") (pinfunction "2_P$2") (pintype "passive"))
      (node (ref "U$9") (pin "P$2") (pinfunction "2_P$2") (pintype "passive"))
    )
    (net (code "112") (name "Net-(U$8-3)") (class "Default")
      (node (ref "U$8") (pin "P$3") (pinfunction "3_P$3") (pintype "passive"))
      (node (ref "U$9") (pin "P$3") (pinfunction "3_P$3") (pintype "passive"))
    )
    (net (code "113") (name "Net-(U$8-4)") (class "Default")
      (node (ref "U$8") (pin "P$4") (pinfunction "4_P$4") (pintype "passive"))
      (node (ref "U$9") (pin "P$4") (pinfunction "4_P$4") (pintype "passive"))
    )
    (net (code "114") (name "Net-(U$8-5)") (class "Default")
      (node (ref "U$8") (pin "P$5") (pinfunction "5_P$5") (pintype "passive"))
      (node (ref "U$9") (pin "P$5") (pinfunction "5_P$5") (pintype "passive"))
    )
    (net (code "115") (name "Net-(U$8-6)") (class "Default")
      (node (ref "U$8") (pin "P$6") (pinfunction "6_P$6") (pintype "passive"))
      (node (ref "U$9") (pin "P$6") (pinfunction "6_P$6") (pintype "passive"))
    )
    (net (code "116") (name "Net-(X2-1)") (class "Default")
      (node (ref "C6D0-7") (pin "5") (pinfunction "5_5") (pintype "passive"))
      (node (ref "R1") (pin "1") (pinfunction "1_1") (pintype "passive"))
      (node (ref "X1") (pin "14") (pinfunction "14_14") (pintype "passive"))
      (node (ref "X2") (pin "P$1") (pinfunction "1_P$1") (pintype "passive"))
    )
    (net (code "117") (name "Net-(X3-1)") (class "Default")
      (node (ref "C6D0-7") (pin "6") (pinfunction "6_6") (pintype "passive"))
      (node (ref "R2") (pin "1") (pinfunction "1_1") (pintype "passive"))
      (node (ref "X1") (pin "21") (pinfunction "21_21") (pintype "passive"))
      (node (ref "X3") (pin "P$1") (pinfunction "1_P$1") (pintype "passive"))
    )
    (net (code "118") (name "unconnected-(C5A-Pad4)") (class "Default")
      (node (ref "C5A") (pin "4") (pinfunction "4_4") (pintype "passive"))
    )
    (net (code "119") (name "unconnected-(C5A-Pad14)") (class "Default")
      (node (ref "C5A") (pin "14") (pinfunction "14_14") (pintype "passive"))
    )
    (net (code "120") (name "unconnected-(C6D0-7-Pad1)") (class "Default")
      (node (ref "C6D0-7") (pin "1") (pinfunction "1_1") (pintype "passive"))
    )
    (net (code "121") (name "unconnected-(C6D8-13-Pad7)") (class "Default")
      (node (ref "C6D8-13") (pin "7") (pinfunction "7_7") (pintype "passive"))
    )
    (net (code "122") (name "unconnected-(POWER-Pad7)") (class "Default")
      (node (ref "POWER") (pin "7") (pinfunction "7_7") (pintype "passive"))
    )
    (net (code "123") (name "unconnected-(POWER-Pad8)") (class "Default")
      (node (ref "POWER") (pin "8") (pinfunction "8_8") (pintype "passive"))
    )
    (net (code "124") (name "unconnected-(RL1A-3-PadCOM1)") (class "Default")
      (node (ref "RL1") (pin "COM1") (pinfunction "3_COM1") (pintype "passive"))
    )
    (net (code "125") (name "unconnected-(U$4-4-Pad3V)") (class "Default")
      (node (ref "U$4") (pin "3V") (pinfunction "4_3V") (pintype "passive"))
    )
    (net (code "126") (name "unconnected-(U$4-11-PadPGM)") (class "Default")
      (node (ref "U$4") (pin "PGM") (pinfunction "11_PGM") (pintype "passive"))
    )
  )
)
